# MCU.net
KiCad netlist of a schematic drawn in Altium Designer
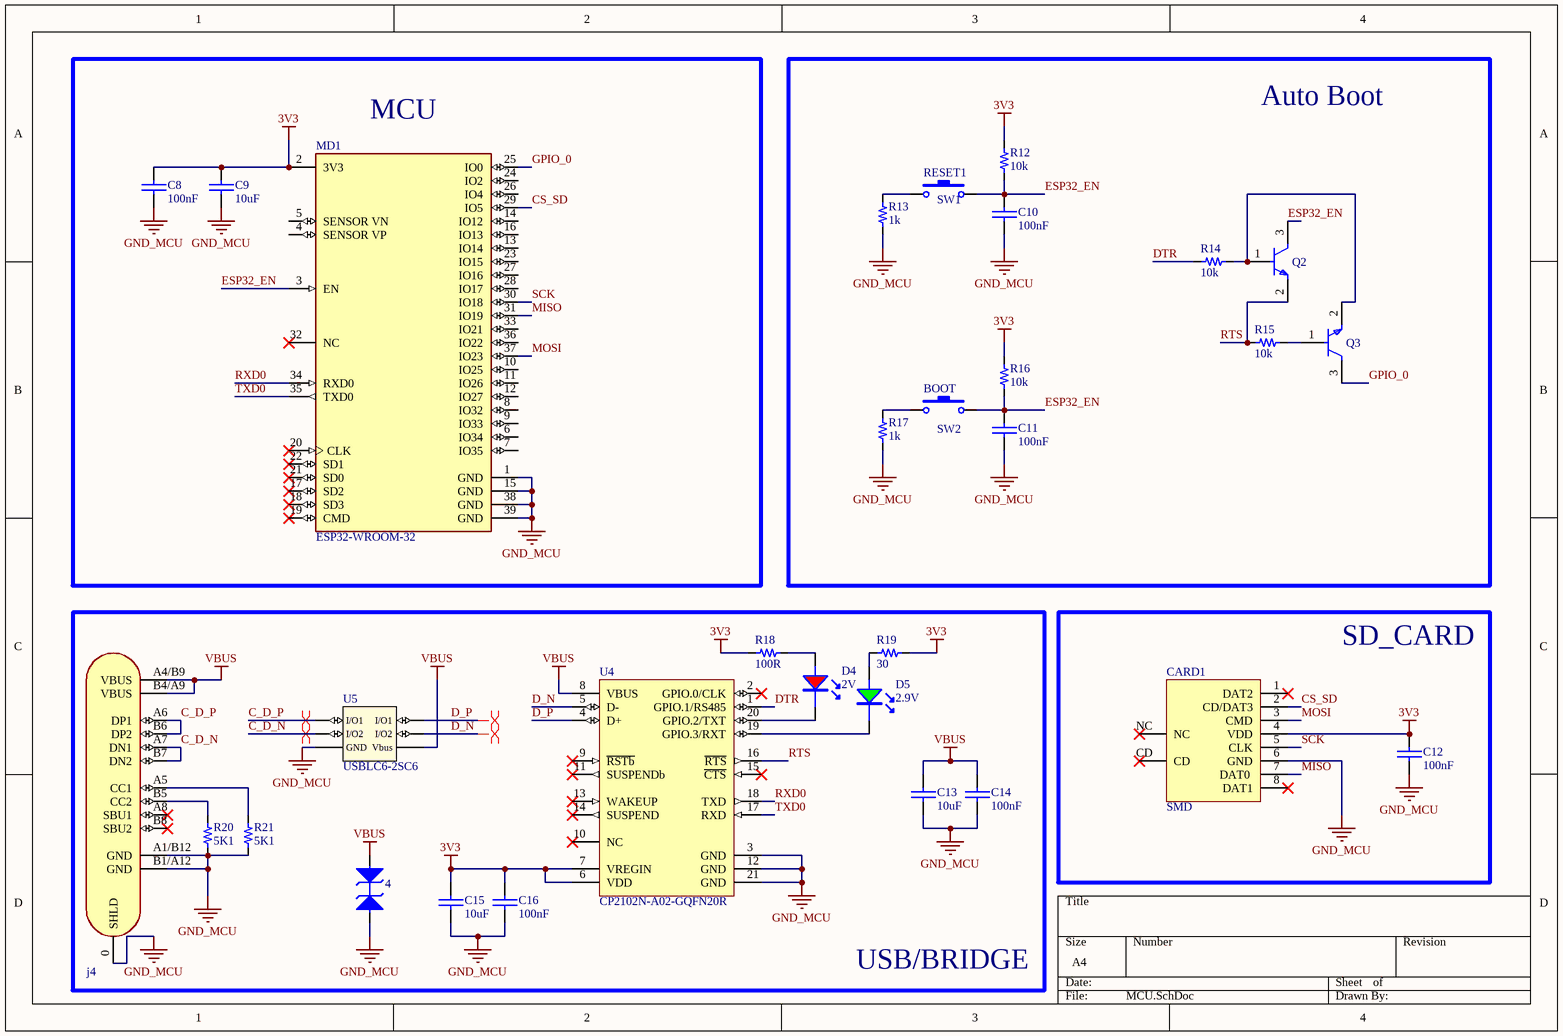
[diagram p0: MCU.SchDoc]

(export (version "E")
  (design (tool "Eeschema 10.0.6"))
  (components
    (comp (ref "4")
      (value "TVS 12V")
      (footprint "SOD_123FL")
      (description "21.7A 200W@10/1000us 9.2V 7V Bidirectional 5V SOD-123FL ESD and Surge Protection (TVS/ESD) ROHS")
      (fields (field (name "MANUFACTURER") "TDSEMIC") (field (name "MANUFACTURER PART NUMBER") "SMF5.0CA"))
      (libsource (lib "CNCLib") (part "TVS_5V_1CH_BID_SOD_123FL"))
    )
    (comp (ref "C8")
      (value "100nF")
      (footprint "0603_cap")
      (description "50V 100nF X7R ±10% 0603 Ceramic Capacitors RoHS")
      (fields
        (field (name "MANUFACTURER") "FOJAN")
        (field (name "MANUFACTURER PART NUMBER") "FCC0603B104K500CT")
      )
      (libsource (lib "CNCLib") (part "Cap_100nF_0603_50V"))
    )
    (comp (ref "C9")
      (value "10uF")
      (footprint "0603_cap")
      (description "10V 10uF X5R ±10% 0603 Multilayer Ceramic Capacitors MLCC - SMD/SMT ROHS")
      (fields
        (field (name "MANUFACTURER") "CCTC")
        (field (name "MANUFACTURER PART NUMBER") "TCC0603X5R106K100CT")
      )
      (libsource (lib "CNCLib") (part "Cap_10uF_0603_10V"))
    )
    (comp (ref "C10")
      (value "100nF")
      (footprint "0603_cap")
      (description "50V 100nF X7R ±10% 0603 Ceramic Capacitors RoHS")
      (fields
        (field (name "MANUFACTURER") "FOJAN")
        (field (name "MANUFACTURER PART NUMBER") "FCC0603B104K500CT")
      )
      (libsource (lib "CNCLib") (part "Cap_100nF_0603_50V"))
    )
    (comp (ref "C11")
      (value "100nF")
      (footprint "0603_cap")
      (description "50V 100nF X7R ±10% 0603 Ceramic Capacitors RoHS")
      (fields
        (field (name "MANUFACTURER") "FOJAN")
        (field (name "MANUFACTURER PART NUMBER") "FCC0603B104K500CT")
      )
      (libsource (lib "CNCLib") (part "Cap_100nF_0603_50V"))
    )
    (comp (ref "C12")
      (value "100nF")
      (footprint "0603_cap")
      (description "50V 100nF X7R ±10% 0603 Ceramic Capacitors RoHS")
      (fields
        (field (name "MANUFACTURER") "FOJAN")
        (field (name "MANUFACTURER PART NUMBER") "FCC0603B104K500CT")
      )
      (libsource (lib "CNCLib") (part "Cap_100nF_0603_50V"))
    )
    (comp (ref "C13")
      (value "10uF")
      (footprint "0603_cap")
      (description "10V 10uF X5R ±10% 0603 Multilayer Ceramic Capacitors MLCC - SMD/SMT ROHS")
      (fields
        (field (name "MANUFACTURER") "CCTC")
        (field (name "MANUFACTURER PART NUMBER") "TCC0603X5R106K100CT")
      )
      (libsource (lib "CNCLib") (part "Cap_10uF_0603_10V"))
    )
    (comp (ref "C14")
      (value "100nF")
      (footprint "0603_cap")
      (description "50V 100nF X7R ±10% 0603 Ceramic Capacitors RoHS")
      (fields
        (field (name "MANUFACTURER") "FOJAN")
        (field (name "MANUFACTURER PART NUMBER") "FCC0603B104K500CT")
      )
      (libsource (lib "CNCLib") (part "Cap_100nF_0603_50V"))
    )
    (comp (ref "C15")
      (value "10uF")
      (footprint "0603_cap")
      (description "10V 10uF X5R ±10% 0603 Multilayer Ceramic Capacitors MLCC - SMD/SMT ROHS")
      (fields
        (field (name "MANUFACTURER") "CCTC")
        (field (name "MANUFACTURER PART NUMBER") "TCC0603X5R106K100CT")
      )
      (libsource (lib "CNCLib") (part "Cap_10uF_0603_10V"))
    )
    (comp (ref "C16")
      (value "100nF")
      (footprint "0603_cap")
      (description "50V 100nF X7R ±10% 0603 Ceramic Capacitors RoHS")
      (fields
        (field (name "MANUFACTURER") "FOJAN")
        (field (name "MANUFACTURER PART NUMBER") "FCC0603B104K500CT")
      )
      (libsource (lib "CNCLib") (part "Cap_100nF_0603_50V"))
    )
    (comp (ref "CARD1")
      (value "SMD")
      (footprint "SD_CARD_PUSH_PCB")
      (description "Push-Push 2mm Connector and Ejector MicroSD Card (TF Card) SMD PC Card Sockets RoHS")
      (fields (field (name "MANUFACTURER") "Yuandi") (field (name "MANUFACTURER PART NUMBER") "TF-01A"))
      (libsource (lib "CNCLib") (part "SD_CARD_PUSH"))
    )
    (comp (ref "D4")
      (value "2V")
      (footprint "0805_LED")
      (description "LED RED CLEAR 0805 SMD")
      (fields
        (field (name "MANUFACTURER") "XINGLIGHT")
        (field (name "MANUFACTURER PART NUMBER") "XL-2012SURC")
      )
      (libsource (lib "CNCLib") (part "LED_0805_RED"))
    )
    (comp (ref "D5")
      (value "2.9V")
      (footprint "0805_LED")
      (description "LED GREEN CLEAR 0805 SMD")
      (fields
        (field (name "MANUFACTURER") "XINGLIGHT")
        (field (name "MANUFACTURER PART NUMBER") "XL-2012UGC")
      )
      (libsource (lib "CNCLib") (part "LED_0805_Green"))
    )
    (comp (ref "j4")
      (value "USB C")
      (footprint "CON_USB_C_16P_RA")
      (description "3A USB 3.1 1 Surface Mount 16P Female -40℃~+85℃ Type-C SMD USB Connectors ROHS")
      (fields
        (field (name "MANUFACTURER") "SHOU HAN")
        (field (name "MANUFACTURER PART NUMBER") "TYPE-C-3.1-16PIN")
      )
      (libsource (lib "CNCLib") (part "CON_USB_TYPEC_16P"))
    )
    (comp (ref "MD1")
      (value "ESP32-WROOM-32")
      (description "WIFI MODULE 32MBITS SPI FLASH")
      (fields
        (field (name "MANUFACTURER") "ESPRESSIF")
        (field (name "MANUFACTURER PART NUMBER") "ESP32-WROOM-32-N4")
      )
      (libsource (lib "CNCLib") (part "CMP-194065-000003-1"))
    )
    (comp (ref "Q2")
      (value "TRANS NPN 40V 200mA SOT-23")
      (description "40V 310mW 200mA NPN SOT-23 Single Bipolar Transistors RoHS")
      (fields (field (name "MANUFACTURER") "DIODES") (field (name "MANUFACTURER PART NUMBER") "MMBT3904-7-F"))
      (libsource (lib "CNCLib") (part "BJT_N_MMBT3904-7-F"))
    )
    (comp (ref "Q3")
      (value "TRANS NPN 40V 200mA SOT-23")
      (description "40V 310mW 200mA NPN SOT-23 Single Bipolar Transistors RoHS")
      (fields (field (name "MANUFACTURER") "DIODES") (field (name "MANUFACTURER PART NUMBER") "MMBT3904-7-F"))
      (libsource (lib "CNCLib") (part "BJT_N_MMBT3904-7-F"))
    )
    (comp (ref "R12")
      (value "10k")
      (footprint "0603_res")
      (description "RES SMD 10k OHM 5% 1/10W 0603")
      (fields (field (name "MANUFACTURER") "FOJAN") (field (name "MANUFACTURER PART NUMBER") "FRC0603J103TS"))
      (libsource (lib "CNCLib") (part "Res_10k_0603_1/10W"))
    )
    (comp (ref "R13")
      (value "1k")
      (footprint "0603_res")
      (description "RES SMD 1k OHM 5% 1/10W 0603")
      (fields
        (field (name "MANUFACTURER") "FOJAN")
        (field (name "MANUFACTURER PART NUMBER") "FRC0603J102 TS")
      )
      (libsource (lib "CNCLib") (part "Res_1k_0603_1/10W"))
    )
    (comp (ref "R14")
      (value "10k")
      (footprint "0603_res")
      (description "RES SMD 10k OHM 5% 1/10W 0603")
      (fields (field (name "MANUFACTURER") "FOJAN") (field (name "MANUFACTURER PART NUMBER") "FRC0603J103TS"))
      (libsource (lib "CNCLib") (part "Res_10k_0603_1/10W"))
    )
    (comp (ref "R15")
      (value "10k")
      (footprint "0603_res")
      (description "RES SMD 10k OHM 5% 1/10W 0603")
      (fields (field (name "MANUFACTURER") "FOJAN") (field (name "MANUFACTURER PART NUMBER") "FRC0603J103TS"))
      (libsource (lib "CNCLib") (part "Res_10k_0603_1/10W"))
    )
    (comp (ref "R16")
      (value "10k")
      (footprint "0603_res")
      (description "RES SMD 10k OHM 5% 1/10W 0603")
      (fields (field (name "MANUFACTURER") "FOJAN") (field (name "MANUFACTURER PART NUMBER") "FRC0603J103TS"))
      (libsource (lib "CNCLib") (part "Res_10k_0603_1/10W"))
    )
    (comp (ref "R17")
      (value "1k")
      (footprint "0603_res")
      (description "RES SMD 1k OHM 5% 1/10W 0603")
      (fields
        (field (name "MANUFACTURER") "FOJAN")
        (field (name "MANUFACTURER PART NUMBER") "FRC0603J102 TS")
      )
      (libsource (lib "CNCLib") (part "Res_1k_0603_1/10W"))
    )
    (comp (ref "R18")
      (value "100R")
      (footprint "0603_res")
      (description "RES SMD 100R OHM 5% 1/10W 0603")
      (fields
        (field (name "MANUFACTURER") "FOJAN")
        (field (name "MANUFACTURER PART NUMBER") "FRC0603J101 TS")
      )
      (libsource (lib "CNCLib") (part "Res_100R_0603_1/10W"))
    )
    (comp (ref "R19")
      (value "30")
      (footprint "0603_res")
      (description "100mW 30Ω 75V ±100ppm/℃ Thick Film Resistor ±5% 0603 Chip Resistor - Surface Mount RoHS")
      (fields
        (field (name "MANUFACTURER") "FOJAN")
        (field (name "MANUFACTURER PART NUMBER") "FRC0603J300 TS")
      )
      (libsource (lib "CNCLib") (part "Res_30_0603_1/10W"))
    )
    (comp (ref "R20")
      (value "5K1")
      (footprint "0603_res")
      (description "100mW 5.1kΩ 75V ±100ppm/℃ Thick Film Resistor ±1% 0603 Chip Resistor - Surface Mount RoHS")
      (fields
        (field (name "MANUFACTURER") "FOJAN")
        (field (name "MANUFACTURER PART NUMBER") "FRC0603F5101TS")
      )
      (libsource (lib "CNCLib") (part "Res 5K1"))
    )
    (comp (ref "R21")
      (value "5K1")
      (footprint "0603_res")
      (description "100mW 5.1kΩ 75V ±100ppm/℃ Thick Film Resistor ±1% 0603 Chip Resistor - Surface Mount RoHS")
      (fields
        (field (name "MANUFACTURER") "FOJAN")
        (field (name "MANUFACTURER PART NUMBER") "FRC0603F5101TS")
      )
      (libsource (lib "CNCLib") (part "Res 5K1"))
    )
    (comp (ref "SW1")
      (value "Sw")
      (footprint "Sw_PUSH_4.5x4.5x5mm")
      (description "SWITCH TACTILE SPST-NO 0.05A 12V")
      (fields
        (field (name "MANUFACTURER") "BZCN")
        (field (name "MANUFACTURER PART NUMBER") "TSC015A05026A")
        (field (name "LAST MODIFIED BY") "N-A.Potosi")
      )
      (libsource (lib "CNCLib") (part "Sw_PUSH_4.5x4.5x5.0xmm"))
    )
    (comp (ref "SW2")
      (value "Sw")
      (footprint "Sw_PUSH_4.5x4.5x5mm")
      (description "SWITCH TACTILE SPST-NO 0.05A 12V")
      (fields
        (field (name "MANUFACTURER") "BZCN")
        (field (name "MANUFACTURER PART NUMBER") "TSC015A05026A")
        (field (name "LAST MODIFIED BY") "N-A.Potosi")
      )
      (libsource (lib "CNCLib") (part "Sw_PUSH_4.5x4.5x5.0xmm"))
    )
    (comp (ref "U4")
      (value "CP2102N-A02-GQFN20R")
      (footprint "WFQFN_20_EP_3X3MM")
      (description "IC USB TO UART BRIDGE QFN20")
      (fields (field (name "MANUFACTURER") "Silicon Labs"))
      (libsource (lib "CNCLib") (part "IC_SGL_USB2UART-BRIDGE_20QFN"))
    )
    (comp (ref "U5")
      (value "USBLC6-2SC6")
      (footprint "SOT_23_6")
      (description "TVS DIODE 5.25V 17V SOT23-6")
      (fields (field (name "MANUFACTURER") "STMicroelectronics"))
      (libsource (lib "CNCLib") (part "TVS_5.25V_2CH_SOT_23_6"))
    )
  )
  (nets
    (net (code "1") (name "/CS_SD") (class "Default")
      (node (ref "CARD1") (pin "2") (pinfunction "CD/DAT3_2") (pintype "passive"))
      (node (ref "MD1") (pin "29") (pinfunction "IO5_29") (pintype "bidirectional"))
    )
    (net (code "2") (name "/C_D_N") (class "Default")
      (node (ref "U5") (pin "3") (pinfunction "I/O2_3") (pintype "bidirectional"))
      (node (ref "j4") (pin "A7") (pinfunction "DN1_A7") (pintype "bidirectional"))
      (node (ref "j4") (pin "B7") (pinfunction "DN2_B7") (pintype "bidirectional"))
    )
    (net (code "3") (name "/C_D_P") (class "Default")
      (node (ref "U5") (pin "1") (pinfunction "I/O1_1") (pintype "bidirectional"))
      (node (ref "j4") (pin "A6") (pinfunction "DP1_A6") (pintype "bidirectional"))
      (node (ref "j4") (pin "B6") (pinfunction "DP2_B6") (pintype "bidirectional"))
    )
    (net (code "4") (name "/DTR") (class "Default")
      (node (ref "R14") (pin "2") (pinfunction "2_2") (pintype "passive"))
      (node (ref "U4") (pin "1") (pinfunction "GPIO.1/RS485_1") (pintype "bidirectional"))
    )
    (net (code "5") (name "/D_N") (class "Default")
      (node (ref "U4") (pin "5") (pinfunction "D-_5") (pintype "bidirectional"))
      (node (ref "U5") (pin "4") (pinfunction "I/O2_4") (pintype "bidirectional"))
    )
    (net (code "6") (name "/D_P") (class "Default")
      (node (ref "U4") (pin "4") (pinfunction "D+_4") (pintype "bidirectional"))
      (node (ref "U5") (pin "6") (pinfunction "I/O1_6") (pintype "bidirectional"))
    )
    (net (code "7") (name "/ESP32_EN") (class "Default")
      (node (ref "C10") (pin "1") (pinfunction "1_1") (pintype "passive"))
      (node (ref "C11") (pin "1") (pinfunction "1_1") (pintype "passive"))
      (node (ref "MD1") (pin "3") (pinfunction "EN_3") (pintype "input"))
      (node (ref "Q2") (pin "3") (pinfunction "C_3") (pintype "passive"))
      (node (ref "R12") (pin "1") (pinfunction "1_1") (pintype "passive"))
      (node (ref "R16") (pin "1") (pinfunction "1_1") (pintype "passive"))
      (node (ref "SW1") (pin "2") (pinfunction "2_2") (pintype "passive"))
      (node (ref "SW2") (pin "2") (pinfunction "2_2") (pintype "passive"))
    )
    (net (code "8") (name "/GPIO_0") (class "Default")
      (node (ref "MD1") (pin "25") (pinfunction "IO0_25") (pintype "bidirectional"))
      (node (ref "Q3") (pin "3") (pinfunction "C_3") (pintype "passive"))
    )
    (net (code "9") (name "/MISO") (class "Default")
      (node (ref "CARD1") (pin "7") (pinfunction "DAT0_7") (pintype "passive"))
      (node (ref "MD1") (pin "31") (pinfunction "IO19_31") (pintype "bidirectional"))
    )
    (net (code "10") (name "/MOSI") (class "Default")
      (node (ref "CARD1") (pin "3") (pinfunction "CMD_3") (pintype "passive"))
      (node (ref "MD1") (pin "37") (pinfunction "IO23_37") (pintype "bidirectional"))
    )
    (net (code "11") (name "/RTS") (class "Default")
      (node (ref "Q2") (pin "2") (pinfunction "E_2") (pintype "passive"))
      (node (ref "R15") (pin "2") (pinfunction "2_2") (pintype "passive"))
      (node (ref "U4") (pin "16") (pinfunction "~{RTS}_16") (pintype "output"))
    )
    (net (code "12") (name "/RXD0") (class "Default")
      (node (ref "MD1") (pin "34") (pinfunction "RXD0_34") (pintype "input"))
      (node (ref "U4") (pin "18") (pinfunction "TXD_18") (pintype "output"))
    )
    (net (code "13") (name "/SCK") (class "Default")
      (node (ref "CARD1") (pin "5") (pinfunction "CLK_5") (pintype "passive"))
      (node (ref "MD1") (pin "30") (pinfunction "IO18_30") (pintype "bidirectional"))
    )
    (net (code "14") (name "/TXD0") (class "Default")
      (node (ref "MD1") (pin "35") (pinfunction "TXD0_35") (pintype "output"))
      (node (ref "U4") (pin "17") (pinfunction "RXD_17") (pintype "input"))
    )
    (net (code "15") (name "3V3") (class "Default")
      (node (ref "C12") (pin "1") (pinfunction "1_1") (pintype "passive"))
      (node (ref "C15") (pin "1") (pinfunction "1_1") (pintype "passive"))
      (node (ref "C16") (pin "1") (pinfunction "1_1") (pintype "passive"))
      (node (ref "C8") (pin "1") (pinfunction "1_1") (pintype "passive"))
      (node (ref "C9") (pin "1") (pinfunction "1_1") (pintype "passive"))
      (node (ref "CARD1") (pin "4") (pinfunction "VDD_4") (pintype "passive"))
      (node (ref "MD1") (pin "2") (pinfunction "3V3_2") (pintype "power_in"))
      (node (ref "R12") (pin "2") (pinfunction "2_2") (pintype "passive"))
      (node (ref "R16") (pin "2") (pinfunction "2_2") (pintype "passive"))
      (node (ref "R18") (pin "1") (pinfunction "1_1") (pintype "passive"))
      (node (ref "R19") (pin "2") (pinfunction "2_2") (pintype "passive"))
      (node (ref "U4") (pin "6") (pinfunction "VDD_6") (pintype "power_in"))
      (node (ref "U4") (pin "7") (pinfunction "VREGIN_7") (pintype "power_in"))
    )
    (net (code "16") (name "GND_MCU") (class "Default")
      (node (ref "4") (pin "2") (pinfunction "2_2") (pintype "passive"))
      (node (ref "C10") (pin "2") (pinfunction "2_2") (pintype "passive"))
      (node (ref "C11") (pin "2") (pinfunction "2_2") (pintype "passive"))
      (node (ref "C12") (pin "2") (pinfunction "2_2") (pintype "passive"))
      (node (ref "C13") (pin "2") (pinfunction "2_2") (pintype "passive"))
      (node (ref "C14") (pin "2") (pinfunction "2_2") (pintype "passive"))
      (node (ref "C15") (pin "2") (pinfunction "2_2") (pintype "passive"))
      (node (ref "C16") (pin "2") (pinfunction "2_2") (pintype "passive"))
      (node (ref "C8") (pin "2") (pinfunction "2_2") (pintype "passive"))
      (node (ref "C9") (pin "2") (pinfunction "2_2") (pintype "passive"))
      (node (ref "CARD1") (pin "6") (pinfunction "GND_6") (pintype "passive"))
      (node (ref "MD1") (pin "1") (pinfunction "GND_1") (pintype "power_in"))
      (node (ref "MD1") (pin "15") (pinfunction "GND_15") (pintype "power_in"))
      (node (ref "MD1") (pin "38") (pinfunction "GND_38") (pintype "power_in"))
      (node (ref "MD1") (pin "39") (pinfunction "GND_39") (pintype "power_in"))
      (node (ref "R13") (pin "1") (pinfunction "1_1") (pintype "passive"))
      (node (ref "R17") (pin "1") (pinfunction "1_1") (pintype "passive"))
      (node (ref "R20") (pin "1") (pinfunction "1_1") (pintype "passive"))
      (node (ref "R21") (pin "1") (pinfunction "1_1") (pintype "passive"))
      (node (ref "U4") (pin "12") (pinfunction "GND_12") (pintype "power_in"))
      (node (ref "U4") (pin "21") (pinfunction "GND_21") (pintype "power_in"))
      (node (ref "U4") (pin "3") (pinfunction "GND_3") (pintype "power_in"))
      (node (ref "U5") (pin "2") (pinfunction "GND_2") (pintype "power_in"))
      (node (ref "j4") (pin "0") (pinfunction "SHLD_0") (pintype "passive"))
      (node (ref "j4") (pin "A1/B12") (pinfunction "GND_A1/B12") (pintype "power_in"))
      (node (ref "j4") (pin "B1/A12") (pinfunction "GND_B1/A12") (pintype "power_in"))
    )
    (net (code "17") (name "Net-(D4-A)") (class "Default")
      (node (ref "D4") (pin "1") (pinfunction "A_1") (pintype "passive"))
      (node (ref "R18") (pin "2") (pinfunction "2_2") (pintype "passive"))
    )
    (net (code "18") (name "Net-(D5-A)") (class "Default")
      (node (ref "D5") (pin "1") (pinfunction "A_1") (pintype "passive"))
      (node (ref "R19") (pin "1") (pinfunction "1_1") (pintype "passive"))
    )
    (net (code "19") (name "Net-(Q2-B)") (class "Default")
      (node (ref "Q2") (pin "1") (pinfunction "B_1") (pintype "passive"))
      (node (ref "Q3") (pin "2") (pinfunction "E_2") (pintype "passive"))
      (node (ref "R14") (pin "1") (pinfunction "1_1") (pintype "passive"))
    )
    (net (code "20") (name "Net-(Q3-B)") (class "Default")
      (node (ref "Q3") (pin "1") (pinfunction "B_1") (pintype "passive"))
      (node (ref "R15") (pin "1") (pinfunction "1_1") (pintype "passive"))
    )
    (net (code "21") (name "Net-(R13-Pad2)") (class "Default")
      (node (ref "R13") (pin "2") (pinfunction "2_2") (pintype "passive"))
      (node (ref "SW1") (pin "1") (pinfunction "1_1") (pintype "passive"))
    )
    (net (code "22") (name "Net-(R17-Pad2)") (class "Default")
      (node (ref "R17") (pin "2") (pinfunction "2_2") (pintype "passive"))
      (node (ref "SW2") (pin "1") (pinfunction "1_1") (pintype "passive"))
    )
    (net (code "23") (name "Net-(U4-GPIO.2{slash}TXT)") (class "Default")
      (node (ref "D4") (pin "2") (pinfunction "2_2") (pintype "passive"))
      (node (ref "U4") (pin "20") (pinfunction "GPIO.2/TXT_20") (pintype "bidirectional"))
    )
    (net (code "24") (name "Net-(U4-GPIO.3{slash}RXT)") (class "Default")
      (node (ref "D5") (pin "2") (pinfunction "2_2") (pintype "passive"))
      (node (ref "U4") (pin "19") (pinfunction "GPIO.3/RXT_19") (pintype "bidirectional"))
    )
    (net (code "25") (name "Net-(j4-CC1)") (class "Default")
      (node (ref "R21") (pin "2") (pinfunction "2_2") (pintype "passive"))
      (node (ref "j4") (pin "A5") (pinfunction "CC1_A5") (pintype "bidirectional"))
    )
    (net (code "26") (name "Net-(j4-CC2)") (class "Default")
      (node (ref "R20") (pin "2") (pinfunction "2_2") (pintype "passive"))
      (node (ref "j4") (pin "B5") (pinfunction "CC2_B5") (pintype "bidirectional"))
    )
    (net (code "27") (name "VBUS") (class "Default")
      (node (ref "4") (pin "1") (pinfunction "1_1") (pintype "passive"))
      (node (ref "C13") (pin "1") (pinfunction "1_1") (pintype "passive"))
      (node (ref "C14") (pin "1") (pinfunction "1_1") (pintype "passive"))
      (node (ref "U4") (pin "8") (pinfunction "VBUS_8") (pintype "power_in"))
      (node (ref "U5") (pin "5") (pinfunction "Vbus_5") (pintype "power_in"))
      (node (ref "j4") (pin "A4/B9") (pinfunction "VBUS_A4/B9") (pintype "power_in"))
      (node (ref "j4") (pin "B4/A9") (pinfunction "VBUS_B4/A9") (pintype "power_in"))
    )
    (net (code "28") (name "unconnected-(CARD1-DAT1-Pad8)") (class "Default")
      (node (ref "CARD1") (pin "8") (pinfunction "DAT1_8") (pintype "passive+no_connect"))
    )
    (net (code "29") (name "unconnected-(CARD1-DAT2-Pad1)") (class "Default")
      (node (ref "CARD1") (pin "1") (pinfunction "DAT2_1") (pintype "passive+no_connect"))
    )
    (net (code "30") (name "unconnected-(CARD1-PadCD)") (class "Default")
      (node (ref "CARD1") (pin "CD") (pinfunction "CD_CD") (pintype "passive+no_connect"))
    )
    (net (code "31") (name "unconnected-(CARD1-PadNC)") (class "Default")
      (node (ref "CARD1") (pin "NC") (pinfunction "NC_NC") (pintype "passive+no_connect"))
    )
    (net (code "32") (name "unconnected-(MD1-CLK-Pad20)") (class "Default")
      (node (ref "MD1") (pin "20") (pinfunction "CLK_20") (pintype "input+no_connect"))
    )
    (net (code "33") (name "unconnected-(MD1-CMD-Pad19)") (class "Default")
      (node (ref "MD1") (pin "19") (pinfunction "CMD_19") (pintype "bidirectional+no_connect"))
    )
    (net (code "34") (name "unconnected-(MD1-IO2-Pad24)") (class "Default")
      (node (ref "MD1") (pin "24") (pinfunction "IO2_24") (pintype "bidirectional"))
    )
    (net (code "35") (name "unconnected-(MD1-IO4-Pad26)") (class "Default")
      (node (ref "MD1") (pin "26") (pinfunction "IO4_26") (pintype "bidirectional"))
    )
    (net (code "36") (name "unconnected-(MD1-IO12-Pad14)") (class "Default")
      (node (ref "MD1") (pin "14") (pinfunction "IO12_14") (pintype "bidirectional"))
    )
    (net (code "37") (name "unconnected-(MD1-IO13-Pad16)") (class "Default")
      (node (ref "MD1") (pin "16") (pinfunction "IO13_16") (pintype "bidirectional"))
    )
    (net (code "38") (name "unconnected-(MD1-IO14-Pad13)") (class "Default")
      (node (ref "MD1") (pin "13") (pinfunction "IO14_13") (pintype "bidirectional"))
    )
    (net (code "39") (name "unconnected-(MD1-IO15-Pad23)") (class "Default")
      (node (ref "MD1") (pin "23") (pinfunction "IO15_23") (pintype "bidirectional"))
    )
    (net (code "40") (name "unconnected-(MD1-IO16-Pad27)") (class "Default")
      (node (ref "MD1") (pin "27") (pinfunction "IO16_27") (pintype "bidirectional"))
    )
    (net (code "41") (name "unconnected-(MD1-IO17-Pad28)") (class "Default")
      (node (ref "MD1") (pin "28") (pinfunction "IO17_28") (pintype "bidirectional"))
    )
    (net (code "42") (name "unconnected-(MD1-IO21-Pad33)") (class "Default")
      (node (ref "MD1") (pin "33") (pinfunction "IO21_33") (pintype "bidirectional"))
    )
    (net (code "43") (name "unconnected-(MD1-IO22-Pad36)") (class "Default")
      (node (ref "MD1") (pin "36") (pinfunction "IO22_36") (pintype "bidirectional"))
    )
    (net (code "44") (name "unconnected-(MD1-IO25-Pad10)") (class "Default")
      (node (ref "MD1") (pin "10") (pinfunction "IO25_10") (pintype "bidirectional"))
    )
    (net (code "45") (name "unconnected-(MD1-IO26-Pad11)") (class "Default")
      (node (ref "MD1") (pin "11") (pinfunction "IO26_11") (pintype "bidirectional"))
    )
    (net (code "46") (name "unconnected-(MD1-IO27-Pad12)") (class "Default")
      (node (ref "MD1") (pin "12") (pinfunction "IO27_12") (pintype "bidirectional"))
    )
    (net (code "47") (name "unconnected-(MD1-IO32-Pad8)") (class "Default")
      (node (ref "MD1") (pin "8") (pinfunction "IO32_8") (pintype "bidirectional"))
    )
    (net (code "48") (name "unconnected-(MD1-IO33-Pad9)") (class "Default")
      (node (ref "MD1") (pin "9") (pinfunction "IO33_9") (pintype "bidirectional"))
    )
    (net (code "49") (name "unconnected-(MD1-IO34-Pad6)") (class "Default")
      (node (ref "MD1") (pin "6") (pinfunction "IO34_6") (pintype "bidirectional"))
    )
    (net (code "50") (name "unconnected-(MD1-IO35-Pad7)") (class "Default")
      (node (ref "MD1") (pin "7") (pinfunction "IO35_7") (pintype "bidirectional"))
    )
    (net (code "51") (name "unconnected-(MD1-NC-Pad32)") (class "Default")
      (node (ref "MD1") (pin "32") (pinfunction "NC_32") (pintype "passive+no_connect"))
    )
    (net (code "52") (name "unconnected-(MD1-SD0-Pad21)") (class "Default")
      (node (ref "MD1") (pin "21") (pinfunction "SD0_21") (pintype "bidirectional+no_connect"))
    )
    (net (code "53") (name "unconnected-(MD1-SD1-Pad22)") (class "Default")
      (node (ref "MD1") (pin "22") (pinfunction "SD1_22") (pintype "bidirectional+no_connect"))
    )
    (net (code "54") (name "unconnected-(MD1-SD2-Pad17)") (class "Default")
      (node (ref "MD1") (pin "17") (pinfunction "SD2_17") (pintype "bidirectional+no_connect"))
    )
    (net (code "55") (name "unconnected-(MD1-SD3-Pad18)") (class "Default")
      (node (ref "MD1") (pin "18") (pinfunction "SD3_18") (pintype "bidirectional+no_connect"))
    )
    (net (code "56") (name "unconnected-(MD1-SENSOR_VN-Pad5)") (class "Default")
      (node (ref "MD1") (pin "5") (pinfunction "SENSOR_VN_5") (pintype "bidirectional"))
    )
    (net (code "57") (name "unconnected-(MD1-SENSOR_VP-Pad4)") (class "Default")
      (node (ref "MD1") (pin "4") (pinfunction "SENSOR_VP_4") (pintype "bidirectional"))
    )
    (net (code "58") (name "unconnected-(U4-GPIO.0{slash}CLK-Pad2)") (class "Default")
      (node (ref "U4") (pin "2") (pinfunction "GPIO.0/CLK_2") (pintype "bidirectional+no_connect"))
    )
    (net (code "59") (name "unconnected-(U4-NC-Pad10)") (class "Default")
      (node (ref "U4") (pin "10") (pinfunction "NC_10") (pintype "passive+no_connect"))
    )
    (net (code "60") (name "unconnected-(U4-SUSPEND-Pad14)") (class "Default")
      (node (ref "U4") (pin "14") (pinfunction "SUSPEND_14") (pintype "output+no_connect"))
    )
    (net (code "61") (name "unconnected-(U4-SUSPENDb-Pad11)") (class "Default")
      (node (ref "U4") (pin "11") (pinfunction "SUSPENDb_11") (pintype "output+no_connect"))
    )
    (net (code "62") (name "unconnected-(U4-WAKEUP-Pad13)") (class "Default")
      (node (ref "U4") (pin "13") (pinfunction "WAKEUP_13") (pintype "input+no_connect"))
    )
    (net (code "63") (name "unconnected-(U4-~{CTS}-Pad15)") (class "Default")
      (node (ref "U4") (pin "15") (pinfunction "~{CTS}_15") (pintype "input+no_connect"))
    )
    (net (code "64") (name "unconnected-(U4-~{RSTb}-Pad9)") (class "Default")
      (node (ref "U4") (pin "9") (pinfunction "~{RSTb}_9") (pintype "input+no_connect"))
    )
    (net (code "65") (name "unconnected-(j4-SBU1-PadA8)") (class "Default")
      (node (ref "j4") (pin "A8") (pinfunction "SBU1_A8") (pintype "bidirectional+no_connect"))
    )
    (net (code "66") (name "unconnected-(j4-SBU2-PadB8)") (class "Default")
      (node (ref "j4") (pin "B8") (pinfunction "SBU2_B8") (pintype "bidirectional+no_connect"))
    )
  )
)
